# Mixer-01.net
KiCad netlist of a schematic drawn in EAGLE
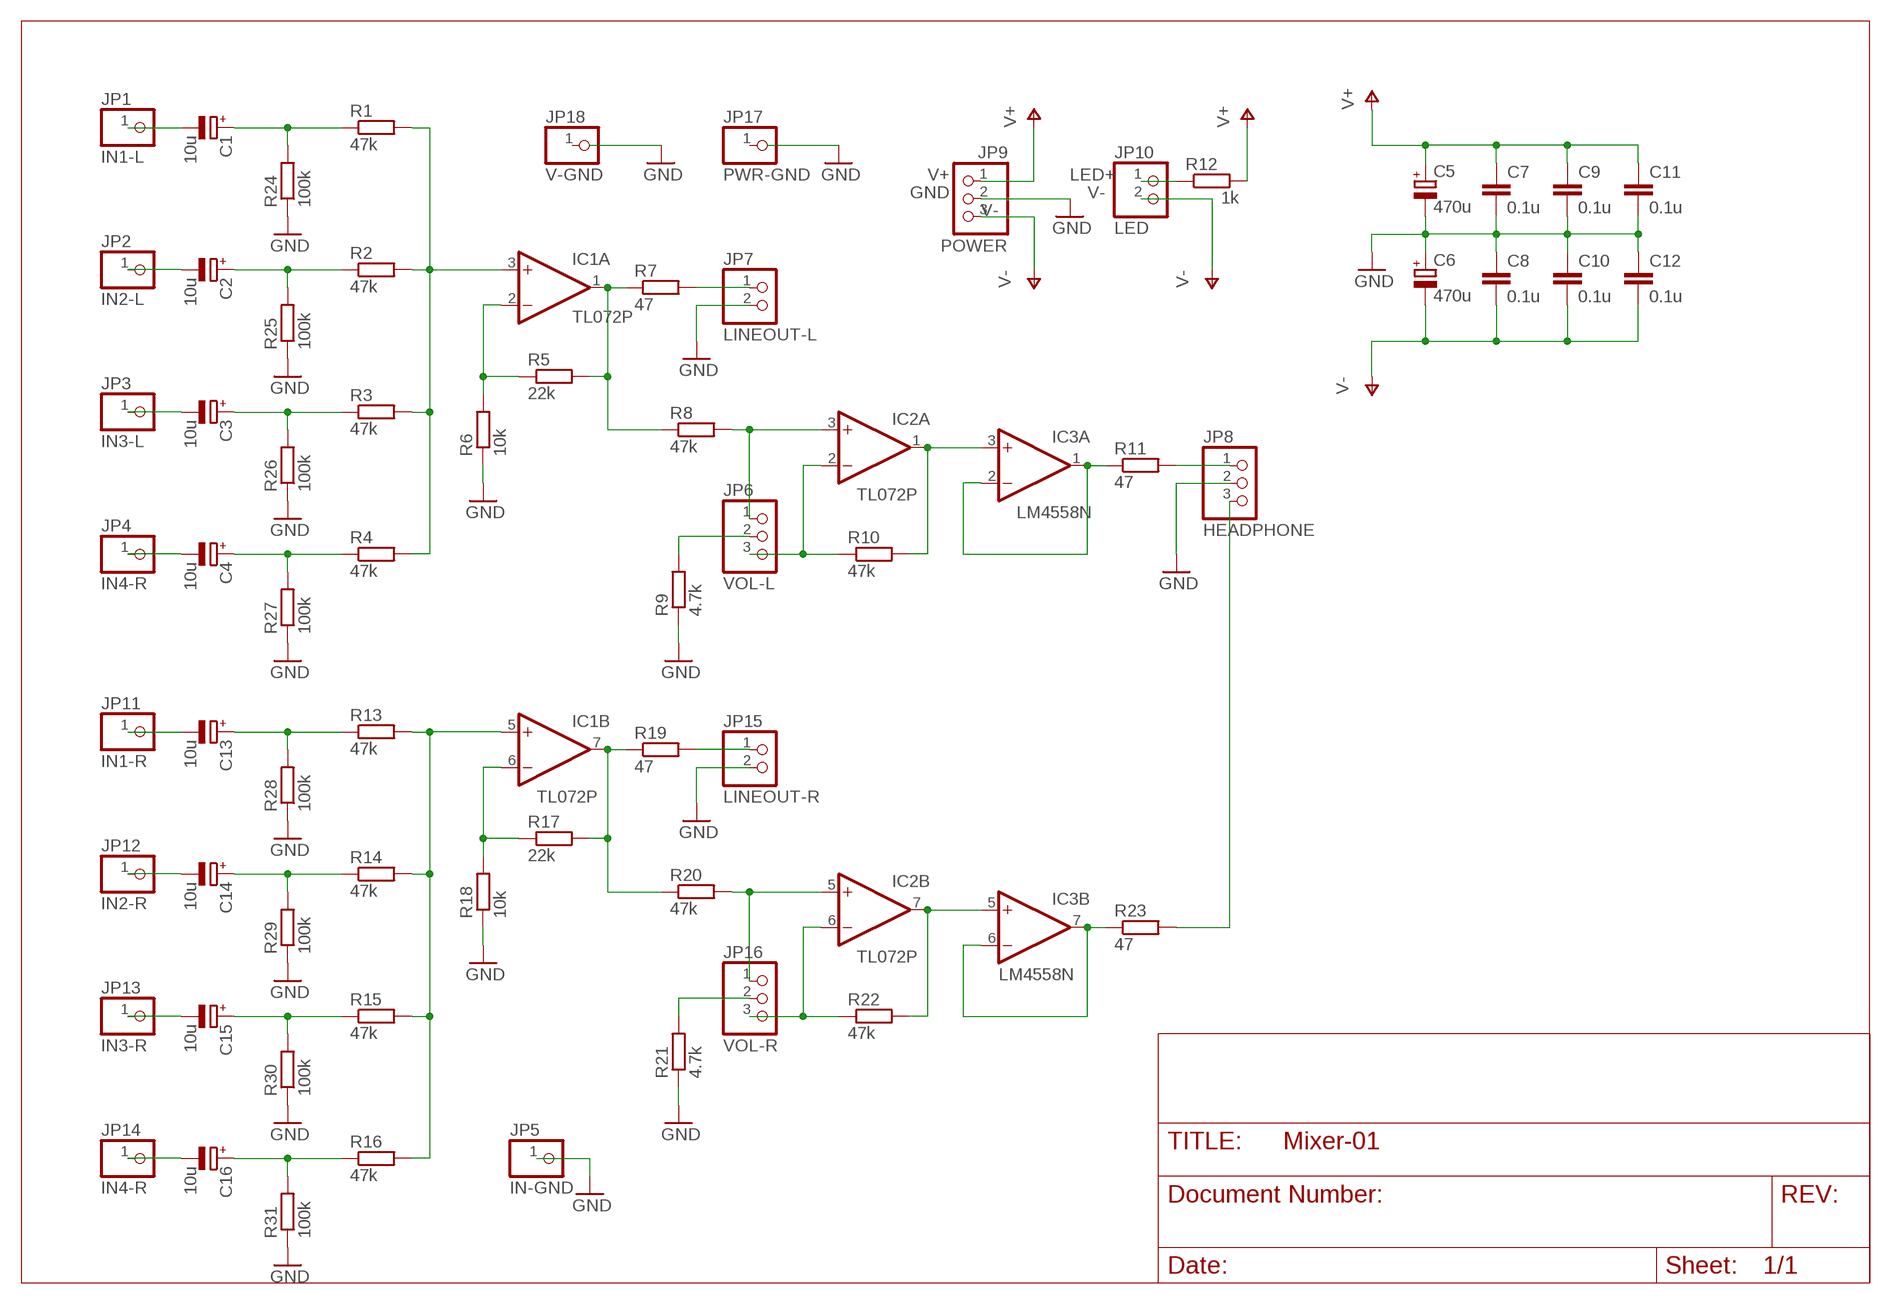
[diagram p0: schematic, sheet 1]

(export (version "E")
  (design (tool "Eeschema 10.0.6"))
  (components
    (comp (ref "C1")
      (value "10u")
      (footprint "eagle-import:E5-8,5")
      (libsource (lib "eagle-import") (part "CPOL-EUE5-8.5"))
    )
    (comp (ref "C2")
      (value "10u")
      (footprint "eagle-import:E5-8,5")
      (libsource (lib "eagle-import") (part "CPOL-EUE5-8.5"))
    )
    (comp (ref "C3")
      (value "10u")
      (footprint "eagle-import:E5-8,5")
      (libsource (lib "eagle-import") (part "CPOL-EUE5-8.5"))
    )
    (comp (ref "C4")
      (value "10u")
      (footprint "eagle-import:E5-8,5")
      (libsource (lib "eagle-import") (part "CPOL-EUE5-8.5"))
    )
    (comp (ref "C5")
      (value "470u")
      (footprint "eagle-import:E7,5-16")
      (libsource (lib "eagle-import") (part "CPOL-EUE7.5-16"))
    )
    (comp (ref "C6")
      (value "470u")
      (footprint "eagle-import:E7,5-16")
      (libsource (lib "eagle-import") (part "CPOL-EUE7.5-16"))
    )
    (comp (ref "C7")
      (value "0.1u")
      (footprint "eagle-import:C050-024X044")
      (libsource (lib "eagle-import") (part "C-EU050-024X044"))
    )
    (comp (ref "C8")
      (value "0.1u")
      (footprint "eagle-import:C050-024X044")
      (libsource (lib "eagle-import") (part "C-EU050-024X044"))
    )
    (comp (ref "C9")
      (value "0.1u")
      (footprint "eagle-import:C050-024X044")
      (libsource (lib "eagle-import") (part "C-EU050-024X044"))
    )
    (comp (ref "C10")
      (value "0.1u")
      (footprint "eagle-import:C050-024X044")
      (libsource (lib "eagle-import") (part "C-EU050-024X044"))
    )
    (comp (ref "C11")
      (value "0.1u")
      (footprint "eagle-import:C050-024X044")
      (libsource (lib "eagle-import") (part "C-EU050-024X044"))
    )
    (comp (ref "C12")
      (value "0.1u")
      (footprint "eagle-import:C050-024X044")
      (libsource (lib "eagle-import") (part "C-EU050-024X044"))
    )
    (comp (ref "C13")
      (value "10u")
      (footprint "eagle-import:E5-8,5")
      (libsource (lib "eagle-import") (part "CPOL-EUE5-8.5"))
    )
    (comp (ref "C14")
      (value "10u")
      (footprint "eagle-import:E5-8,5")
      (libsource (lib "eagle-import") (part "CPOL-EUE5-8.5"))
    )
    (comp (ref "C15")
      (value "10u")
      (footprint "eagle-import:E5-8,5")
      (libsource (lib "eagle-import") (part "CPOL-EUE5-8.5"))
    )
    (comp (ref "C16")
      (value "10u")
      (footprint "eagle-import:E5-8,5")
      (libsource (lib "eagle-import") (part "CPOL-EUE5-8.5"))
    )
    (comp (ref "IC1")
      (value "TL072P")
      (footprint "eagle-import:DIL08")
      (libsource (lib "eagle-import") (part "TL072P"))
    )
    (comp (ref "IC2")
      (value "TL072P")
      (footprint "eagle-import:DIL08")
      (libsource (lib "eagle-import") (part "TL072P"))
    )
    (comp (ref "IC3")
      (value "LM4558N")
      (footprint "eagle-import:DIL08")
      (libsource (lib "eagle-import") (part "4558NLM"))
    )
    (comp (ref "JP1")
      (value "IN1-L")
      (footprint "eagle-import:1X01")
      (libsource (lib "eagle-import") (part "PINHD-1X1"))
    )
    (comp (ref "JP2")
      (value "IN2-L")
      (footprint "eagle-import:1X01")
      (libsource (lib "eagle-import") (part "PINHD-1X1"))
    )
    (comp (ref "JP3")
      (value "IN3-L")
      (footprint "eagle-import:1X01")
      (libsource (lib "eagle-import") (part "PINHD-1X1"))
    )
    (comp (ref "JP4")
      (value "IN4-R")
      (footprint "eagle-import:1X01")
      (libsource (lib "eagle-import") (part "PINHD-1X1"))
    )
    (comp (ref "JP5")
      (value "IN-GND")
      (footprint "eagle-import:1X01")
      (libsource (lib "eagle-import") (part "PINHD-1X1"))
    )
    (comp (ref "JP6")
      (value "VOL-L")
      (footprint "eagle-import:1X03")
      (libsource (lib "eagle-import") (part "PINHD-1X3"))
    )
    (comp (ref "JP7")
      (value "LINEOUT-L")
      (footprint "eagle-import:1X02")
      (libsource (lib "eagle-import") (part "PINHD-1X2"))
    )
    (comp (ref "JP8")
      (value "HEADPHONE")
      (footprint "eagle-import:1X03")
      (libsource (lib "eagle-import") (part "PINHD-1X3"))
    )
    (comp (ref "JP9")
      (value "POWER")
      (footprint "eagle-import:1X03")
      (libsource (lib "eagle-import") (part "PINHD-1X3"))
    )
    (comp (ref "JP10")
      (value "LED")
      (footprint "eagle-import:1X02")
      (libsource (lib "eagle-import") (part "PINHD-1X2"))
    )
    (comp (ref "JP11")
      (value "IN1-R")
      (footprint "eagle-import:1X01")
      (libsource (lib "eagle-import") (part "PINHD-1X1"))
    )
    (comp (ref "JP12")
      (value "IN2-R")
      (footprint "eagle-import:1X01")
      (libsource (lib "eagle-import") (part "PINHD-1X1"))
    )
    (comp (ref "JP13")
      (value "IN3-R")
      (footprint "eagle-import:1X01")
      (libsource (lib "eagle-import") (part "PINHD-1X1"))
    )
    (comp (ref "JP14")
      (value "IN4-R")
      (footprint "eagle-import:1X01")
      (libsource (lib "eagle-import") (part "PINHD-1X1"))
    )
    (comp (ref "JP15")
      (value "LINEOUT-R")
      (footprint "eagle-import:1X02")
      (libsource (lib "eagle-import") (part "PINHD-1X2"))
    )
    (comp (ref "JP16")
      (value "VOL-R")
      (footprint "eagle-import:1X03")
      (libsource (lib "eagle-import") (part "PINHD-1X3"))
    )
    (comp (ref "JP17")
      (value "PWR-GND")
      (footprint "eagle-import:1X01")
      (libsource (lib "eagle-import") (part "PINHD-1X1"))
    )
    (comp (ref "JP18")
      (value "V-GND")
      (footprint "eagle-import:1X01")
      (libsource (lib "eagle-import") (part "PINHD-1X1"))
    )
    (comp (ref "R1")
      (value "47k")
      (footprint "eagle-import:0207_7")
      (libsource (lib "eagle-import") (part "resistor_R-EU_0207/7"))
    )
    (comp (ref "R2")
      (value "47k")
      (footprint "eagle-import:0207_7")
      (libsource (lib "eagle-import") (part "resistor_R-EU_0207/7"))
    )
    (comp (ref "R3")
      (value "47k")
      (footprint "eagle-import:0207_7")
      (libsource (lib "eagle-import") (part "resistor_R-EU_0207/7"))
    )
    (comp (ref "R4")
      (value "47k")
      (footprint "eagle-import:0207_7")
      (libsource (lib "eagle-import") (part "resistor_R-EU_0207/7"))
    )
    (comp (ref "R5")
      (value "22k")
      (footprint "eagle-import:0207_7")
      (libsource (lib "eagle-import") (part "resistor_R-EU_0207/7"))
    )
    (comp (ref "R6")
      (value "10k")
      (footprint "eagle-import:0207_7")
      (libsource (lib "eagle-import") (part "resistor_R-EU_0207/7"))
    )
    (comp (ref "R7")
      (value "47")
      (footprint "eagle-import:0207_7")
      (libsource (lib "eagle-import") (part "resistor_R-EU_0207/7"))
    )
    (comp (ref "R8")
      (value "47k")
      (footprint "eagle-import:0207_7")
      (libsource (lib "eagle-import") (part "resistor_R-EU_0207/7"))
    )
    (comp (ref "R9")
      (value "4.7k")
      (footprint "eagle-import:0207_7")
      (libsource (lib "eagle-import") (part "resistor_R-EU_0207/7"))
    )
    (comp (ref "R10")
      (value "47k")
      (footprint "eagle-import:0207_7")
      (libsource (lib "eagle-import") (part "resistor_R-EU_0207/7"))
    )
    (comp (ref "R11")
      (value "47")
      (footprint "eagle-import:0207_7")
      (libsource (lib "eagle-import") (part "resistor_R-EU_0207/7"))
    )
    (comp (ref "R12")
      (value "1k")
      (footprint "eagle-import:0207_7")
      (libsource (lib "eagle-import") (part "resistor_R-EU_0207/7"))
    )
    (comp (ref "R13")
      (value "47k")
      (footprint "eagle-import:0207_7")
      (libsource (lib "eagle-import") (part "resistor_R-EU_0207/7"))
    )
    (comp (ref "R14")
      (value "47k")
      (footprint "eagle-import:0207_7")
      (libsource (lib "eagle-import") (part "resistor_R-EU_0207/7"))
    )
    (comp (ref "R15")
      (value "47k")
      (footprint "eagle-import:0207_7")
      (libsource (lib "eagle-import") (part "resistor_R-EU_0207/7"))
    )
    (comp (ref "R16")
      (value "47k")
      (footprint "eagle-import:0207_7")
      (libsource (lib "eagle-import") (part "resistor_R-EU_0207/7"))
    )
    (comp (ref "R17")
      (value "22k")
      (footprint "eagle-import:0207_7")
      (libsource (lib "eagle-import") (part "resistor_R-EU_0207/7"))
    )
    (comp (ref "R18")
      (value "10k")
      (footprint "eagle-import:0207_7")
      (libsource (lib "eagle-import") (part "resistor_R-EU_0207/7"))
    )
    (comp (ref "R19")
      (value "47")
      (footprint "eagle-import:0207_7")
      (libsource (lib "eagle-import") (part "resistor_R-EU_0207/7"))
    )
    (comp (ref "R20")
      (value "47k")
      (footprint "eagle-import:0207_7")
      (libsource (lib "eagle-import") (part "resistor_R-EU_0207/7"))
    )
    (comp (ref "R21")
      (value "4.7k")
      (footprint "eagle-import:0207_7")
      (libsource (lib "eagle-import") (part "resistor_R-EU_0207/7"))
    )
    (comp (ref "R22")
      (value "47k")
      (footprint "eagle-import:0207_7")
      (libsource (lib "eagle-import") (part "resistor_R-EU_0207/7"))
    )
    (comp (ref "R23")
      (value "47")
      (footprint "eagle-import:0207_7")
      (libsource (lib "eagle-import") (part "resistor_R-EU_0207/7"))
    )
    (comp (ref "R24")
      (value "100k")
      (footprint "eagle-import:0207_7")
      (libsource (lib "eagle-import") (part "R-EU_0207/7"))
    )
    (comp (ref "R25")
      (value "100k")
      (footprint "eagle-import:0207_7")
      (libsource (lib "eagle-import") (part "R-EU_0207/7"))
    )
    (comp (ref "R26")
      (value "100k")
      (footprint "eagle-import:0207_7")
      (libsource (lib "eagle-import") (part "R-EU_0207/7"))
    )
    (comp (ref "R27")
      (value "100k")
      (footprint "eagle-import:0207_7")
      (libsource (lib "eagle-import") (part "R-EU_0207/7"))
    )
    (comp (ref "R28")
      (value "100k")
      (footprint "eagle-import:0207_7")
      (libsource (lib "eagle-import") (part "R-EU_0207/7"))
    )
    (comp (ref "R29")
      (value "100k")
      (footprint "eagle-import:0207_7")
      (libsource (lib "eagle-import") (part "R-EU_0207/7"))
    )
    (comp (ref "R30")
      (value "100k")
      (footprint "eagle-import:0207_7")
      (libsource (lib "eagle-import") (part "R-EU_0207/7"))
    )
    (comp (ref "R31")
      (value "100k")
      (footprint "eagle-import:0207_7")
      (libsource (lib "eagle-import") (part "R-EU_0207/7"))
    )
  )
  (nets
    (net (code "1") (name "/LED+") (class "Default")
      (node (ref "JP10") (pin "1") (pinfunction "1_1") (pintype "passive"))
      (node (ref "R12") (pin "1") (pinfunction "1_1") (pintype "passive"))
    )
    (net (code "2") (name "GND") (class "Default")
      (node (ref "C10") (pin "1") (pinfunction "1_1") (pintype "passive"))
      (node (ref "C11") (pin "2") (pinfunction "2_2") (pintype "passive"))
      (node (ref "C12") (pin "1") (pinfunction "1_1") (pintype "passive"))
      (node (ref "C5") (pin "-") (pinfunction "-_-") (pintype "passive"))
      (node (ref "C6") (pin "+") (pinfunction "+_+") (pintype "passive"))
      (node (ref "C7") (pin "2") (pinfunction "2_2") (pintype "passive"))
      (node (ref "C8") (pin "1") (pinfunction "1_1") (pintype "passive"))
      (node (ref "C9") (pin "2") (pinfunction "2_2") (pintype "passive"))
      (node (ref "JP15") (pin "2") (pinfunction "2_2") (pintype "passive"))
      (node (ref "JP5") (pin "1") (pinfunction "1_1") (pintype "passive"))
      (node (ref "JP7") (pin "2") (pinfunction "2_2") (pintype "passive"))
      (node (ref "JP8") (pin "2") (pinfunction "2_2") (pintype "passive"))
      (node (ref "JP9") (pin "2") (pinfunction "2_2") (pintype "passive"))
      (node (ref "R18") (pin "1") (pinfunction "1_1") (pintype "passive"))
      (node (ref "R21") (pin "1") (pinfunction "1_1") (pintype "passive"))
      (node (ref "R24") (pin "1") (pinfunction "1_1") (pintype "passive"))
      (node (ref "R25") (pin "1") (pinfunction "1_1") (pintype "passive"))
      (node (ref "R26") (pin "1") (pinfunction "1_1") (pintype "passive"))
      (node (ref "R27") (pin "1") (pinfunction "1_1") (pintype "passive"))
      (node (ref "R28") (pin "1") (pinfunction "1_1") (pintype "passive"))
      (node (ref "R29") (pin "1") (pinfunction "1_1") (pintype "passive"))
      (node (ref "R30") (pin "1") (pinfunction "1_1") (pintype "passive"))
      (node (ref "R31") (pin "1") (pinfunction "1_1") (pintype "passive"))
      (node (ref "R6") (pin "1") (pinfunction "1_1") (pintype "passive"))
      (node (ref "R9") (pin "1") (pinfunction "1_1") (pintype "passive"))
    )
    (net (code "3") (name "Net-(C1-Pad+)") (class "Default")
      (node (ref "C1") (pin "+") (pinfunction "+_+") (pintype "passive"))
      (node (ref "R1") (pin "1") (pinfunction "1_1") (pintype "passive"))
      (node (ref "R24") (pin "2") (pinfunction "2_2") (pintype "passive"))
    )
    (net (code "4") (name "Net-(C1-Pad-)") (class "Default")
      (node (ref "C1") (pin "-") (pinfunction "-_-") (pintype "passive"))
      (node (ref "JP1") (pin "1") (pinfunction "1_1") (pintype "passive"))
    )
    (net (code "5") (name "Net-(C2-Pad+)") (class "Default")
      (node (ref "C2") (pin "+") (pinfunction "+_+") (pintype "passive"))
      (node (ref "R2") (pin "1") (pinfunction "1_1") (pintype "passive"))
      (node (ref "R25") (pin "2") (pinfunction "2_2") (pintype "passive"))
    )
    (net (code "6") (name "Net-(C2-Pad-)") (class "Default")
      (node (ref "C2") (pin "-") (pinfunction "-_-") (pintype "passive"))
      (node (ref "JP2") (pin "1") (pinfunction "1_1") (pintype "passive"))
    )
    (net (code "7") (name "Net-(C3-Pad+)") (class "Default")
      (node (ref "C3") (pin "+") (pinfunction "+_+") (pintype "passive"))
      (node (ref "R26") (pin "2") (pinfunction "2_2") (pintype "passive"))
      (node (ref "R3") (pin "1") (pinfunction "1_1") (pintype "passive"))
    )
    (net (code "8") (name "Net-(C3-Pad-)") (class "Default")
      (node (ref "C3") (pin "-") (pinfunction "-_-") (pintype "passive"))
      (node (ref "JP3") (pin "1") (pinfunction "1_1") (pintype "passive"))
    )
    (net (code "9") (name "Net-(C4-Pad+)") (class "Default")
      (node (ref "C4") (pin "+") (pinfunction "+_+") (pintype "passive"))
      (node (ref "R27") (pin "2") (pinfunction "2_2") (pintype "passive"))
      (node (ref "R4") (pin "1") (pinfunction "1_1") (pintype "passive"))
    )
    (net (code "10") (name "Net-(C4-Pad-)") (class "Default")
      (node (ref "C4") (pin "-") (pinfunction "-_-") (pintype "passive"))
      (node (ref "JP4") (pin "1") (pinfunction "1_1") (pintype "passive"))
    )
    (net (code "11") (name "Net-(C13-Pad+)") (class "Default")
      (node (ref "C13") (pin "+") (pinfunction "+_+") (pintype "passive"))
      (node (ref "R13") (pin "1") (pinfunction "1_1") (pintype "passive"))
      (node (ref "R28") (pin "2") (pinfunction "2_2") (pintype "passive"))
    )
    (net (code "12") (name "Net-(C13-Pad-)") (class "Default")
      (node (ref "C13") (pin "-") (pinfunction "-_-") (pintype "passive"))
      (node (ref "JP11") (pin "1") (pinfunction "1_1") (pintype "passive"))
    )
    (net (code "13") (name "Net-(C14-Pad+)") (class "Default")
      (node (ref "C14") (pin "+") (pinfunction "+_+") (pintype "passive"))
      (node (ref "R14") (pin "1") (pinfunction "1_1") (pintype "passive"))
      (node (ref "R29") (pin "2") (pinfunction "2_2") (pintype "passive"))
    )
    (net (code "14") (name "Net-(C14-Pad-)") (class "Default")
      (node (ref "C14") (pin "-") (pinfunction "-_-") (pintype "passive"))
      (node (ref "JP12") (pin "1") (pinfunction "1_1") (pintype "passive"))
    )
    (net (code "15") (name "Net-(C15-Pad+)") (class "Default")
      (node (ref "C15") (pin "+") (pinfunction "+_+") (pintype "passive"))
      (node (ref "R15") (pin "1") (pinfunction "1_1") (pintype "passive"))
      (node (ref "R30") (pin "2") (pinfunction "2_2") (pintype "passive"))
    )
    (net (code "16") (name "Net-(C15-Pad-)") (class "Default")
      (node (ref "C15") (pin "-") (pinfunction "-_-") (pintype "passive"))
      (node (ref "JP13") (pin "1") (pinfunction "1_1") (pintype "passive"))
    )
    (net (code "17") (name "Net-(C16-Pad+)") (class "Default")
      (node (ref "C16") (pin "+") (pinfunction "+_+") (pintype "passive"))
      (node (ref "R16") (pin "1") (pinfunction "1_1") (pintype "passive"))
      (node (ref "R31") (pin "2") (pinfunction "2_2") (pintype "passive"))
    )
    (net (code "18") (name "Net-(C16-Pad-)") (class "Default")
      (node (ref "C16") (pin "-") (pinfunction "-_-") (pintype "passive"))
      (node (ref "JP14") (pin "1") (pinfunction "1_1") (pintype "passive"))
    )
    (net (code "19") (name "Net-(IC1A-+IN)") (class "Default")
      (node (ref "IC1") (pin "3") (pinfunction "+IN_3") (pintype "input"))
      (node (ref "R1") (pin "2") (pinfunction "2_2") (pintype "passive"))
      (node (ref "R2") (pin "2") (pinfunction "2_2") (pintype "passive"))
      (node (ref "R3") (pin "2") (pinfunction "2_2") (pintype "passive"))
      (node (ref "R4") (pin "2") (pinfunction "2_2") (pintype "passive"))
    )
    (net (code "20") (name "Net-(IC1A--IN)") (class "Default")
      (node (ref "IC1") (pin "2") (pinfunction "-IN_2") (pintype "input"))
      (node (ref "R5") (pin "1") (pinfunction "1_1") (pintype "passive"))
      (node (ref "R6") (pin "2") (pinfunction "2_2") (pintype "passive"))
    )
    (net (code "21") (name "Net-(IC1A-OUT)") (class "Default")
      (node (ref "IC1") (pin "1") (pinfunction "OUT_1") (pintype "output"))
      (node (ref "R5") (pin "2") (pinfunction "2_2") (pintype "passive"))
      (node (ref "R7") (pin "1") (pinfunction "1_1") (pintype "passive"))
      (node (ref "R8") (pin "1") (pinfunction "1_1") (pintype "passive"))
    )
    (net (code "22") (name "Net-(IC1B-+IN)") (class "Default")
      (node (ref "IC1") (pin "5") (pinfunction "+IN_5") (pintype "input"))
      (node (ref "R13") (pin "2") (pinfunction "2_2") (pintype "passive"))
      (node (ref "R14") (pin "2") (pinfunction "2_2") (pintype "passive"))
      (node (ref "R15") (pin "2") (pinfunction "2_2") (pintype "passive"))
      (node (ref "R16") (pin "2") (pinfunction "2_2") (pintype "passive"))
    )
    (net (code "23") (name "Net-(IC1B--IN)") (class "Default")
      (node (ref "IC1") (pin "6") (pinfunction "-IN_6") (pintype "input"))
      (node (ref "R17") (pin "1") (pinfunction "1_1") (pintype "passive"))
      (node (ref "R18") (pin "2") (pinfunction "2_2") (pintype "passive"))
    )
    (net (code "24") (name "Net-(IC1B-OUT)") (class "Default")
      (node (ref "IC1") (pin "7") (pinfunction "OUT_7") (pintype "output"))
      (node (ref "R17") (pin "2") (pinfunction "2_2") (pintype "passive"))
      (node (ref "R19") (pin "1") (pinfunction "1_1") (pintype "passive"))
      (node (ref "R20") (pin "1") (pinfunction "1_1") (pintype "passive"))
    )
    (net (code "25") (name "Net-(IC2A-+IN)") (class "Default")
      (node (ref "IC2") (pin "3") (pinfunction "+IN_3") (pintype "input"))
      (node (ref "JP6") (pin "1") (pinfunction "1_1") (pintype "passive"))
      (node (ref "R8") (pin "2") (pinfunction "2_2") (pintype "passive"))
    )
    (net (code "26") (name "Net-(IC2A--IN)") (class "Default")
      (node (ref "IC2") (pin "2") (pinfunction "-IN_2") (pintype "input"))
      (node (ref "JP6") (pin "3") (pinfunction "3_3") (pintype "passive"))
      (node (ref "R10") (pin "1") (pinfunction "1_1") (pintype "passive"))
    )
    (net (code "27") (name "Net-(IC2A-OUT)") (class "Default")
      (node (ref "IC2") (pin "1") (pinfunction "OUT_1") (pintype "output"))
      (node (ref "IC3") (pin "3") (pinfunction "+IN_3") (pintype "input"))
      (node (ref "R10") (pin "2") (pinfunction "2_2") (pintype "passive"))
    )
    (net (code "28") (name "Net-(IC2B-+IN)") (class "Default")
      (node (ref "IC2") (pin "5") (pinfunction "+IN_5") (pintype "input"))
      (node (ref "JP16") (pin "1") (pinfunction "1_1") (pintype "passive"))
      (node (ref "R20") (pin "2") (pinfunction "2_2") (pintype "passive"))
    )
    (net (code "29") (name "Net-(IC2B--IN)") (class "Default")
      (node (ref "IC2") (pin "6") (pinfunction "-IN_6") (pintype "input"))
      (node (ref "JP16") (pin "3") (pinfunction "3_3") (pintype "passive"))
      (node (ref "R22") (pin "1") (pinfunction "1_1") (pintype "passive"))
    )
    (net (code "30") (name "Net-(IC2B-OUT)") (class "Default")
      (node (ref "IC2") (pin "7") (pinfunction "OUT_7") (pintype "output"))
      (node (ref "IC3") (pin "5") (pinfunction "+IN_5") (pintype "input"))
      (node (ref "R22") (pin "2") (pinfunction "2_2") (pintype "passive"))
    )
    (net (code "31") (name "Net-(IC3A--IN)") (class "Default")
      (node (ref "IC3") (pin "1") (pinfunction "OUT_1") (pintype "output"))
      (node (ref "IC3") (pin "2") (pinfunction "-IN_2") (pintype "input"))
      (node (ref "R11") (pin "1") (pinfunction "1_1") (pintype "passive"))
    )
    (net (code "32") (name "Net-(IC3B--IN)") (class "Default")
      (node (ref "IC3") (pin "6") (pinfunction "-IN_6") (pintype "input"))
      (node (ref "IC3") (pin "7") (pinfunction "OUT_7") (pintype "output"))
      (node (ref "R23") (pin "1") (pinfunction "1_1") (pintype "passive"))
    )
    (net (code "33") (name "Net-(JP6-Pad2)") (class "Default")
      (node (ref "JP6") (pin "2") (pinfunction "2_2") (pintype "passive"))
      (node (ref "R9") (pin "2") (pinfunction "2_2") (pintype "passive"))
    )
    (net (code "34") (name "Net-(JP7-Pad1)") (class "Default")
      (node (ref "JP7") (pin "1") (pinfunction "1_1") (pintype "passive"))
      (node (ref "R7") (pin "2") (pinfunction "2_2") (pintype "passive"))
    )
    (net (code "35") (name "Net-(JP8-Pad1)") (class "Default")
      (node (ref "JP8") (pin "1") (pinfunction "1_1") (pintype "passive"))
      (node (ref "R11") (pin "2") (pinfunction "2_2") (pintype "passive"))
    )
    (net (code "36") (name "Net-(JP8-Pad3)") (class "Default")
      (node (ref "JP8") (pin "3") (pinfunction "3_3") (pintype "passive"))
      (node (ref "R23") (pin "2") (pinfunction "2_2") (pintype "passive"))
    )
    (net (code "37") (name "Net-(JP15-Pad1)") (class "Default")
      (node (ref "JP15") (pin "1") (pinfunction "1_1") (pintype "passive"))
      (node (ref "R19") (pin "2") (pinfunction "2_2") (pintype "passive"))
    )
    (net (code "38") (name "Net-(JP16-Pad2)") (class "Default")
      (node (ref "JP16") (pin "2") (pinfunction "2_2") (pintype "passive"))
      (node (ref "R21") (pin "2") (pinfunction "2_2") (pintype "passive"))
    )
    (net (code "39") (name "V+") (class "Default")
      (node (ref "C11") (pin "1") (pinfunction "1_1") (pintype "passive"))
      (node (ref "C5") (pin "+") (pinfunction "+_+") (pintype "passive"))
      (node (ref "C7") (pin "1") (pinfunction "1_1") (pintype "passive"))
      (node (ref "C9") (pin "1") (pinfunction "1_1") (pintype "passive"))
      (node (ref "JP9") (pin "1") (pinfunction "1_1") (pintype "passive"))
      (node (ref "R12") (pin "2") (pinfunction "2_2") (pintype "passive"))
    )
    (net (code "40") (name "V-") (class "Default")
      (node (ref "C10") (pin "2") (pinfunction "2_2") (pintype "passive"))
      (node (ref "C12") (pin "2") (pinfunction "2_2") (pintype "passive"))
      (node (ref "C6") (pin "-") (pinfunction "-_-") (pintype "passive"))
      (node (ref "C8") (pin "2") (pinfunction "2_2") (pintype "passive"))
      (node (ref "JP10") (pin "2") (pinfunction "2_2") (pintype "passive"))
      (node (ref "JP9") (pin "3") (pinfunction "3_3") (pintype "passive"))
    )
    (net (code "41") (name "unconnected-(JP17-Pad1)") (class "Default")
      (node (ref "JP17") (pin "1") (pinfunction "1_1") (pintype "passive"))
    )
    (net (code "42") (name "unconnected-(JP18-Pad1)") (class "Default")
      (node (ref "JP18") (pin "1") (pinfunction "1_1") (pintype "passive"))
    )
  )
)
